# fduino.net
KiCad netlist of a schematic drawn in EAGLE
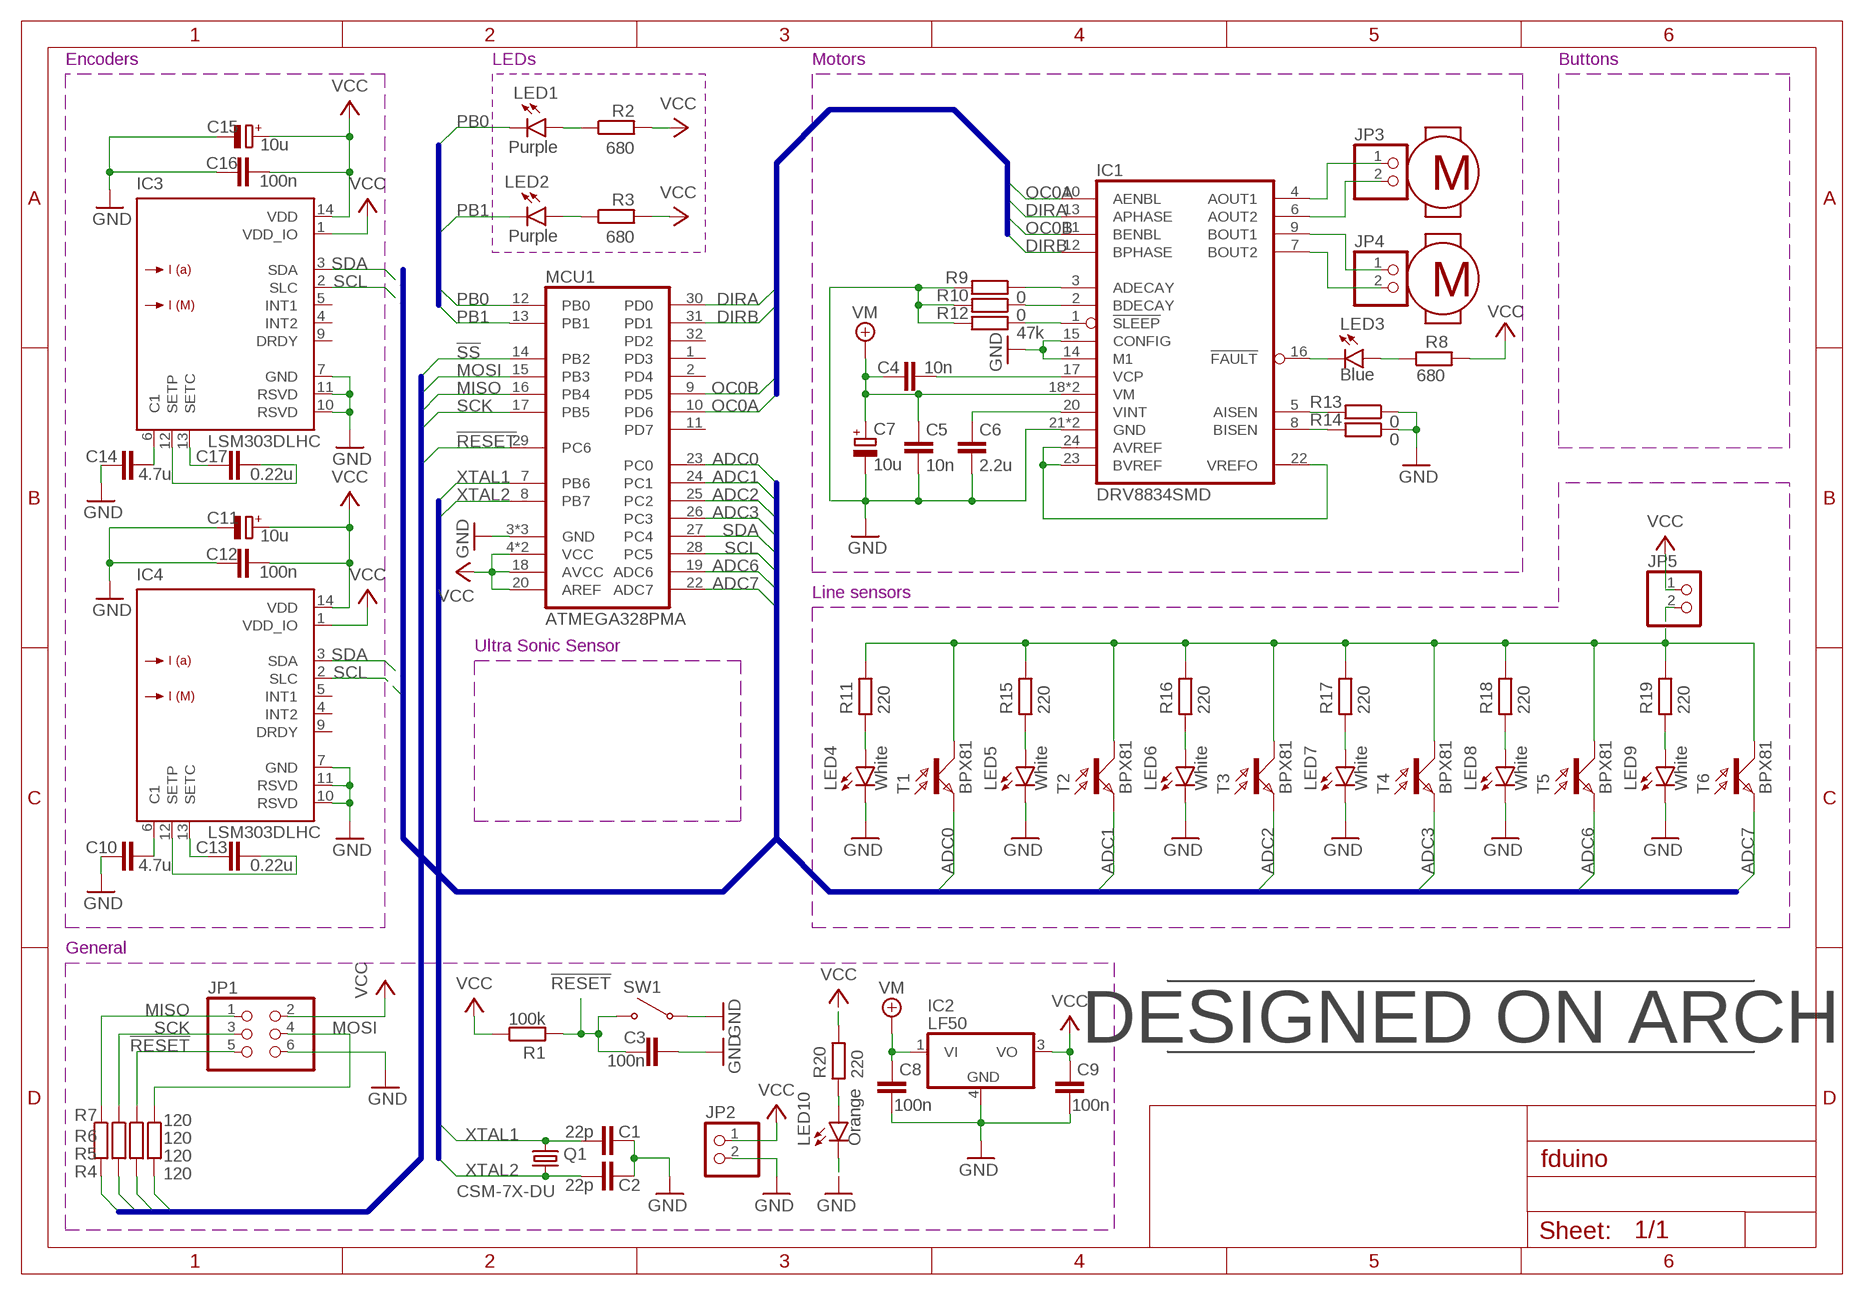
[diagram p0: schematic, sheet 1]

(export (version "E")
  (design (tool "Eeschema 10.0.6"))
  (components
    (comp (ref "C1")
      (value "22p")
      (footprint "eagle-import:C0603")
      (libsource (lib "eagle-import") (part "C-EUC0603"))
    )
    (comp (ref "C2")
      (value "22p")
      (footprint "eagle-import:C0603")
      (libsource (lib "eagle-import") (part "C-EUC0603"))
    )
    (comp (ref "C3")
      (value "100n")
      (footprint "eagle-import:C0603")
      (libsource (lib "eagle-import") (part "C-EUC0603"))
    )
    (comp (ref "C4")
      (value "10n")
      (footprint "eagle-import:C0603")
      (libsource (lib "eagle-import") (part "C-EUC0603"))
    )
    (comp (ref "C5")
      (value "10n")
      (footprint "eagle-import:C0603")
      (libsource (lib "eagle-import") (part "C-EUC0603"))
    )
    (comp (ref "C6")
      (value "2.2u")
      (footprint "eagle-import:C0603")
      (libsource (lib "eagle-import") (part "C-EUC0603"))
    )
    (comp (ref "C7")
      (value "10u")
      (footprint "eagle-import:SMC_Z")
      (libsource (lib "eagle-import") (part "CPOL-EUSMCZ"))
    )
    (comp (ref "C8")
      (value "100n")
      (footprint "eagle-import:C0603")
      (libsource (lib "eagle-import") (part "C-EUC0603"))
    )
    (comp (ref "C9")
      (value "100n")
      (footprint "eagle-import:C0603")
      (libsource (lib "eagle-import") (part "C-EUC0603"))
    )
    (comp (ref "C10")
      (value "4.7u")
      (footprint "eagle-import:C0603")
      (libsource (lib "eagle-import") (part "C-EUC0603"))
    )
    (comp (ref "C11")
      (value "10u")
      (footprint "eagle-import:SMC_Z")
      (libsource (lib "eagle-import") (part "CPOL-EUSMCZ"))
    )
    (comp (ref "C12")
      (value "100n")
      (footprint "eagle-import:C0603")
      (libsource (lib "eagle-import") (part "C-EUC0603"))
    )
    (comp (ref "C13")
      (value "0.22u")
      (footprint "eagle-import:C0603")
      (libsource (lib "eagle-import") (part "C-EUC0603"))
    )
    (comp (ref "C14")
      (value "4.7u")
      (footprint "eagle-import:C0603")
      (libsource (lib "eagle-import") (part "C-EUC0603"))
    )
    (comp (ref "C15")
      (value "10u")
      (footprint "eagle-import:SMC_Z")
      (libsource (lib "eagle-import") (part "CPOL-EUSMCZ"))
    )
    (comp (ref "C16")
      (value "100n")
      (footprint "eagle-import:C0603")
      (libsource (lib "eagle-import") (part "C-EUC0603"))
    )
    (comp (ref "C17")
      (value "0.22u")
      (footprint "eagle-import:C0603")
      (libsource (lib "eagle-import") (part "C-EUC0603"))
    )
    (comp (ref "IC1")
      (value "DRV8834SMD")
      (footprint "eagle-import:HTSSOP")
      (libsource (lib "eagle-import") (part "DRV8834SMD"))
    )
    (comp (ref "IC2")
      (value "LF50")
      (footprint "eagle-import:SOT223")
      (libsource (lib "eagle-import") (part "LM340?-MP05"))
    )
    (comp (ref "IC3")
      (value "LSM303DLHC")
      (footprint "eagle-import:LGA-14")
      (libsource (lib "eagle-import") (part "LSM303DLHC"))
    )
    (comp (ref "IC4")
      (value "LSM303DLHC")
      (footprint "eagle-import:LGA-14")
      (libsource (lib "eagle-import") (part "LSM303DLHC"))
    )
    (comp (ref "JP1")
      (value "PINHD-2X3")
      (footprint "eagle-import:2X03")
      (libsource (lib "eagle-import") (part "PINHD-2X3"))
    )
    (comp (ref "JP2")
      (value "PINHD-1X2")
      (footprint "eagle-import:1X02")
      (libsource (lib "eagle-import") (part "PINHD-1X2"))
    )
    (comp (ref "JP3")
      (value "PINHD-1X2")
      (footprint "eagle-import:1X02")
      (libsource (lib "eagle-import") (part "PINHD-1X2"))
    )
    (comp (ref "JP4")
      (value "PINHD-1X2")
      (footprint "eagle-import:1X02")
      (libsource (lib "eagle-import") (part "PINHD-1X2"))
    )
    (comp (ref "JP5")
      (value "PINHD-1X2")
      (footprint "eagle-import:1X02")
      (libsource (lib "eagle-import") (part "PINHD-1X2"))
    )
    (comp (ref "LED1")
      (value "Purple")
      (footprint "eagle-import:SML0603")
      (libsource (lib "eagle-import") (part "LEDSML0603"))
    )
    (comp (ref "LED2")
      (value "Purple")
      (footprint "eagle-import:SML0603")
      (libsource (lib "eagle-import") (part "LEDSML0603"))
    )
    (comp (ref "LED3")
      (value "Blue")
      (footprint "eagle-import:SML0603")
      (libsource (lib "eagle-import") (part "LEDSML0603"))
    )
    (comp (ref "LED4")
      (value "White")
      (footprint "eagle-import:SML0603")
      (libsource (lib "eagle-import") (part "LEDSML0603"))
    )
    (comp (ref "LED5")
      (value "White")
      (footprint "eagle-import:SML0603")
      (libsource (lib "eagle-import") (part "LEDSML0603"))
    )
    (comp (ref "LED6")
      (value "White")
      (footprint "eagle-import:SML0603")
      (libsource (lib "eagle-import") (part "LEDSML0603"))
    )
    (comp (ref "LED7")
      (value "White")
      (footprint "eagle-import:SML0603")
      (libsource (lib "eagle-import") (part "LEDSML0603"))
    )
    (comp (ref "LED8")
      (value "White")
      (footprint "eagle-import:SML0603")
      (libsource (lib "eagle-import") (part "LEDSML0603"))
    )
    (comp (ref "LED9")
      (value "White")
      (footprint "eagle-import:SML0603")
      (libsource (lib "eagle-import") (part "LEDSML0603"))
    )
    (comp (ref "LED10")
      (value "Orange")
      (footprint "eagle-import:SML0603")
      (libsource (lib "eagle-import") (part "LEDSML0603"))
    )
    (comp (ref "MCU1")
      (value "ATMEGA328PMA")
      (footprint "eagle-import:TQFP32")
      (libsource (lib "eagle-import") (part "ATMEGA328PMA"))
    )
    (comp (ref "Q1")
      (value "CSM-7X-DU")
      (footprint "eagle-import:CSM-7X-DU")
      (libsource (lib "eagle-import") (part "CSM-7X-DU"))
    )
    (comp (ref "R1")
      (value "100k")
      (footprint "eagle-import:R0603")
      (libsource (lib "eagle-import") (part "R-EU_R0603"))
    )
    (comp (ref "R2")
      (value "680")
      (footprint "eagle-import:R0603")
      (libsource (lib "eagle-import") (part "R-EU_R0603"))
    )
    (comp (ref "R3")
      (value "680")
      (footprint "eagle-import:R0603")
      (libsource (lib "eagle-import") (part "R-EU_R0603"))
    )
    (comp (ref "R4")
      (value "120")
      (footprint "eagle-import:R0603")
      (libsource (lib "eagle-import") (part "R-EU_R0603"))
    )
    (comp (ref "R5")
      (value "120")
      (footprint "eagle-import:R0603")
      (libsource (lib "eagle-import") (part "R-EU_R0603"))
    )
    (comp (ref "R6")
      (value "120")
      (footprint "eagle-import:R0603")
      (libsource (lib "eagle-import") (part "R-EU_R0603"))
    )
    (comp (ref "R7")
      (value "120")
      (footprint "eagle-import:R0603")
      (libsource (lib "eagle-import") (part "R-EU_R0603"))
    )
    (comp (ref "R8")
      (value "680")
      (footprint "eagle-import:R0603")
      (libsource (lib "eagle-import") (part "R-EU_R0603"))
    )
    (comp (ref "R9")
      (value "0")
      (footprint "eagle-import:R0603")
      (libsource (lib "eagle-import") (part "R-EU_R0603"))
    )
    (comp (ref "R10")
      (value "0")
      (footprint "eagle-import:R0603")
      (libsource (lib "eagle-import") (part "R-EU_R0603"))
    )
    (comp (ref "R11")
      (value "220")
      (footprint "eagle-import:R0603")
      (libsource (lib "eagle-import") (part "R-EU_R0603"))
    )
    (comp (ref "R12")
      (value "47k")
      (footprint "eagle-import:R0603")
      (libsource (lib "eagle-import") (part "R-EU_R0603"))
    )
    (comp (ref "R13")
      (value "0")
      (footprint "eagle-import:R0603")
      (libsource (lib "eagle-import") (part "R-EU_R0603"))
    )
    (comp (ref "R14")
      (value "0")
      (footprint "eagle-import:R0603")
      (libsource (lib "eagle-import") (part "R-EU_R0603"))
    )
    (comp (ref "R15")
      (value "220")
      (footprint "eagle-import:R0603")
      (libsource (lib "eagle-import") (part "R-EU_R0603"))
    )
    (comp (ref "R16")
      (value "220")
      (footprint "eagle-import:R0603")
      (libsource (lib "eagle-import") (part "R-EU_R0603"))
    )
    (comp (ref "R17")
      (value "220")
      (footprint "eagle-import:R0603")
      (libsource (lib "eagle-import") (part "R-EU_R0603"))
    )
    (comp (ref "R18")
      (value "220")
      (footprint "eagle-import:R0603")
      (libsource (lib "eagle-import") (part "R-EU_R0603"))
    )
    (comp (ref "R19")
      (value "220")
      (footprint "eagle-import:R0603")
      (libsource (lib "eagle-import") (part "R-EU_R0603"))
    )
    (comp (ref "R20")
      (value "220")
      (footprint "eagle-import:R0603")
      (libsource (lib "eagle-import") (part "R-EU_R0603"))
    )
    (comp (ref "SW1")
      (value "SWITCHTHT")
      (footprint "eagle-import:SWITCH")
      (libsource (lib "eagle-import") (part "SWITCHTHT"))
    )
    (comp (ref "T1")
      (value "BPX81")
      (footprint "eagle-import:BPX81")
      (libsource (lib "eagle-import") (part "BPX81"))
    )
    (comp (ref "T2")
      (value "BPX81")
      (footprint "eagle-import:BPX81")
      (libsource (lib "eagle-import") (part "BPX81"))
    )
    (comp (ref "T3")
      (value "BPX81")
      (footprint "eagle-import:BPX81")
      (libsource (lib "eagle-import") (part "BPX81"))
    )
    (comp (ref "T4")
      (value "BPX81")
      (footprint "eagle-import:BPX81")
      (libsource (lib "eagle-import") (part "BPX81"))
    )
    (comp (ref "T5")
      (value "BPX81")
      (footprint "eagle-import:BPX81")
      (libsource (lib "eagle-import") (part "BPX81"))
    )
    (comp (ref "T6")
      (value "BPX81")
      (footprint "eagle-import:BPX81")
      (libsource (lib "eagle-import") (part "BPX81"))
    )
  )
  (nets
    (net (code "1") (name "/ADC0") (class "Default")
      (node (ref "MCU1") (pin "23") (pinfunction "PC0_23") (pintype "bidirectional"))
      (node (ref "T1") (pin "E") (pinfunction "E_E") (pintype "passive"))
    )
    (net (code "2") (name "/ADC1") (class "Default")
      (node (ref "MCU1") (pin "24") (pinfunction "PC1_24") (pintype "bidirectional"))
      (node (ref "T2") (pin "E") (pinfunction "E_E") (pintype "passive"))
    )
    (net (code "3") (name "/ADC2") (class "Default")
      (node (ref "MCU1") (pin "25") (pinfunction "PC2_25") (pintype "bidirectional"))
      (node (ref "T3") (pin "E") (pinfunction "E_E") (pintype "passive"))
    )
    (net (code "4") (name "/ADC3") (class "Default")
      (node (ref "MCU1") (pin "26") (pinfunction "PC3_26") (pintype "bidirectional"))
      (node (ref "T4") (pin "E") (pinfunction "E_E") (pintype "passive"))
    )
    (net (code "5") (name "/ADC6") (class "Default")
      (node (ref "MCU1") (pin "19") (pinfunction "ADC6_19") (pintype "bidirectional"))
      (node (ref "T5") (pin "E") (pinfunction "E_E") (pintype "passive"))
    )
    (net (code "6") (name "/ADC7") (class "Default")
      (node (ref "MCU1") (pin "22") (pinfunction "ADC7_22") (pintype "bidirectional"))
      (node (ref "T6") (pin "E") (pinfunction "E_E") (pintype "passive"))
    )
    (net (code "7") (name "/DIRA") (class "Default")
      (node (ref "IC1") (pin "13") (pinfunction "APHASE_13") (pintype "input"))
      (node (ref "MCU1") (pin "30") (pinfunction "PD0_30") (pintype "bidirectional"))
    )
    (net (code "8") (name "/DIRB") (class "Default")
      (node (ref "IC1") (pin "12") (pinfunction "BPHASE_12") (pintype "input"))
      (node (ref "MCU1") (pin "31") (pinfunction "PD1_31") (pintype "bidirectional"))
    )
    (net (code "9") (name "/MISO") (class "Default")
      (node (ref "JP1") (pin "1") (pinfunction "1_1") (pintype "passive"))
      (node (ref "MCU1") (pin "16") (pinfunction "PB4_16") (pintype "bidirectional"))
      (node (ref "R7") (pin "1") (pinfunction "1_1") (pintype "passive"))
      (node (ref "R7") (pin "2") (pinfunction "2_2") (pintype "passive"))
    )
    (net (code "10") (name "/MOSI") (class "Default")
      (node (ref "JP1") (pin "4") (pinfunction "4_4") (pintype "passive"))
      (node (ref "MCU1") (pin "15") (pinfunction "PB3_15") (pintype "bidirectional"))
      (node (ref "R4") (pin "1") (pinfunction "1_1") (pintype "passive"))
      (node (ref "R4") (pin "2") (pinfunction "2_2") (pintype "passive"))
    )
    (net (code "11") (name "/OC0A") (class "Default")
      (node (ref "IC1") (pin "10") (pinfunction "AENBL_10") (pintype "input"))
      (node (ref "MCU1") (pin "10") (pinfunction "PD6_10") (pintype "bidirectional"))
    )
    (net (code "12") (name "/OC0B") (class "Default")
      (node (ref "IC1") (pin "11") (pinfunction "BENBL_11") (pintype "input"))
      (node (ref "MCU1") (pin "9") (pinfunction "PD5_9") (pintype "bidirectional"))
    )
    (net (code "13") (name "/PB0") (class "Default")
      (node (ref "LED1") (pin "C") (pinfunction "C_C") (pintype "passive"))
      (node (ref "MCU1") (pin "12") (pinfunction "PB0_12") (pintype "bidirectional"))
    )
    (net (code "14") (name "/PB1") (class "Default")
      (node (ref "LED2") (pin "C") (pinfunction "C_C") (pintype "passive"))
      (node (ref "MCU1") (pin "13") (pinfunction "PB1_13") (pintype "bidirectional"))
    )
    (net (code "15") (name "/SCK") (class "Default")
      (node (ref "JP1") (pin "3") (pinfunction "3_3") (pintype "passive"))
      (node (ref "MCU1") (pin "17") (pinfunction "PB5_17") (pintype "output"))
      (node (ref "R6") (pin "1") (pinfunction "1_1") (pintype "passive"))
      (node (ref "R6") (pin "2") (pinfunction "2_2") (pintype "passive"))
    )
    (net (code "16") (name "/SCL") (class "Default")
      (node (ref "IC3") (pin "2") (pinfunction "SLC_2") (pintype "bidirectional"))
      (node (ref "IC4") (pin "2") (pinfunction "SLC_2") (pintype "bidirectional"))
      (node (ref "MCU1") (pin "28") (pinfunction "PC5_28") (pintype "bidirectional"))
    )
    (net (code "17") (name "/SDA") (class "Default")
      (node (ref "IC3") (pin "3") (pinfunction "SDA_3") (pintype "bidirectional"))
      (node (ref "IC4") (pin "3") (pinfunction "SDA_3") (pintype "bidirectional"))
      (node (ref "MCU1") (pin "27") (pinfunction "PC4_27") (pintype "bidirectional"))
    )
    (net (code "18") (name "/XTAL1") (class "Default")
      (node (ref "C1") (pin "2") (pinfunction "2_2") (pintype "passive"))
      (node (ref "MCU1") (pin "7") (pinfunction "PB6_7") (pintype "power_in"))
      (node (ref "Q1") (pin "2") (pinfunction "2_2") (pintype "passive"))
    )
    (net (code "19") (name "/XTAL2") (class "Default")
      (node (ref "C2") (pin "2") (pinfunction "2_2") (pintype "passive"))
      (node (ref "MCU1") (pin "8") (pinfunction "PB7_8") (pintype "input"))
      (node (ref "Q1") (pin "1") (pinfunction "1_1") (pintype "passive"))
    )
    (net (code "20") (name "/~{RESET}") (class "Default")
      (node (ref "C3") (pin "1") (pinfunction "1_1") (pintype "passive"))
      (node (ref "JP1") (pin "5") (pinfunction "5_5") (pintype "passive"))
      (node (ref "MCU1") (pin "29") (pinfunction "PC6_29") (pintype "input"))
      (node (ref "R1") (pin "2") (pinfunction "2_2") (pintype "passive"))
      (node (ref "R5") (pin "1") (pinfunction "1_1") (pintype "passive"))
      (node (ref "R5") (pin "2") (pinfunction "2_2") (pintype "passive"))
      (node (ref "SW1") (pin "P$2") (pinfunction "2_P$2") (pintype "passive"))
    )
    (net (code "21") (name "/~{SS}") (class "Default")
      (node (ref "MCU1") (pin "14") (pinfunction "PB2_14") (pintype "bidirectional"))
    )
    (net (code "22") (name "GND") (class "Default")
      (node (ref "C1") (pin "1") (pinfunction "1_1") (pintype "passive"))
      (node (ref "C10") (pin "2") (pinfunction "2_2") (pintype "passive"))
      (node (ref "C11") (pin "-") (pinfunction "-_-") (pintype "passive"))
      (node (ref "C12") (pin "1") (pinfunction "1_1") (pintype "passive"))
      (node (ref "C14") (pin "2") (pinfunction "2_2") (pintype "passive"))
      (node (ref "C15") (pin "-") (pinfunction "-_-") (pintype "passive"))
      (node (ref "C16") (pin "1") (pinfunction "1_1") (pintype "passive"))
      (node (ref "C2") (pin "1") (pinfunction "1_1") (pintype "passive"))
      (node (ref "C3") (pin "2") (pinfunction "2_2") (pintype "passive"))
      (node (ref "C5") (pin "2") (pinfunction "2_2") (pintype "passive"))
      (node (ref "C6") (pin "2") (pinfunction "2_2") (pintype "passive"))
      (node (ref "C7") (pin "-") (pinfunction "-_-") (pintype "passive"))
      (node (ref "C8") (pin "2") (pinfunction "2_2") (pintype "passive"))
      (node (ref "C9") (pin "2") (pinfunction "2_2") (pintype "passive"))
      (node (ref "IC1") (pin "14") (pinfunction "M1_14") (pintype "input"))
      (node (ref "IC1") (pin "15") (pinfunction "CONFIG_15") (pintype "input"))
      (node (ref "IC1") (pin "21") (pinfunction "GND_21") (pintype "input"))
      (node (ref "IC1") (pin "PPAD") (pinfunction "GND_PPAD") (pintype "input"))
      (node (ref "IC2") (pin "4") (pinfunction "GND_4") (pintype "passive"))
      (node (ref "IC3") (pin "10") (pinfunction "RSVD_10") (pintype "passive"))
      (node (ref "IC3") (pin "11") (pinfunction "RSVD_11") (pintype "passive"))
      (node (ref "IC3") (pin "7") (pinfunction "GND_7") (pintype "power_in"))
      (node (ref "IC4") (pin "10") (pinfunction "RSVD_10") (pintype "passive"))
      (node (ref "IC4") (pin "11") (pinfunction "RSVD_11") (pintype "passive"))
      (node (ref "IC4") (pin "7") (pinfunction "GND_7") (pintype "power_in"))
      (node (ref "JP1") (pin "6") (pinfunction "6_6") (pintype "passive"))
      (node (ref "JP2") (pin "2") (pinfunction "2_2") (pintype "passive"))
      (node (ref "LED10") (pin "C") (pinfunction "C_C") (pintype "passive"))
      (node (ref "LED4") (pin "C") (pinfunction "C_C") (pintype "passive"))
      (node (ref "LED5") (pin "C") (pinfunction "C_C") (pintype "passive"))
      (node (ref "LED6") (pin "C") (pinfunction "C_C") (pintype "passive"))
      (node (ref "LED7") (pin "C") (pinfunction "C_C") (pintype "passive"))
      (node (ref "LED8") (pin "C") (pinfunction "C_C") (pintype "passive"))
      (node (ref "LED9") (pin "C") (pinfunction "C_C") (pintype "passive"))
      (node (ref "MCU1") (pin "21") (pinfunction "GND_21") (pintype "bidirectional"))
      (node (ref "MCU1") (pin "3") (pinfunction "GND_3") (pintype "bidirectional"))
      (node (ref "MCU1") (pin "5") (pinfunction "GND_5") (pintype "bidirectional"))
      (node (ref "R13") (pin "1") (pinfunction "1_1") (pintype "passive"))
      (node (ref "R14") (pin "1") (pinfunction "1_1") (pintype "passive"))
      (node (ref "SW1") (pin "P$1") (pinfunction "1_P$1") (pintype "passive"))
    )
    (net (code "23") (name "Net-(IC1-ADECAY)") (class "Default")
      (node (ref "IC1") (pin "3") (pinfunction "ADECAY_3") (pintype "input"))
      (node (ref "R9") (pin "1") (pinfunction "1_1") (pintype "passive"))
    )
    (net (code "24") (name "Net-(IC1-AISEN)") (class "Default")
      (node (ref "IC1") (pin "5") (pinfunction "AISEN_5") (pintype "output"))
      (node (ref "R13") (pin "2") (pinfunction "2_2") (pintype "passive"))
    )
    (net (code "25") (name "Net-(IC1-AOUT1)") (class "Default")
      (node (ref "IC1") (pin "4") (pinfunction "AOUT1_4") (pintype "output"))
      (node (ref "JP3") (pin "1") (pinfunction "1_1") (pintype "passive"))
    )
    (net (code "26") (name "Net-(IC1-AOUT2)") (class "Default")
      (node (ref "IC1") (pin "6") (pinfunction "AOUT2_6") (pintype "output"))
      (node (ref "JP3") (pin "2") (pinfunction "2_2") (pintype "passive"))
    )
    (net (code "27") (name "Net-(IC1-AVREF)") (class "Default")
      (node (ref "IC1") (pin "22") (pinfunction "VREFO_22") (pintype "output"))
      (node (ref "IC1") (pin "23") (pinfunction "BVREF_23") (pintype "input"))
      (node (ref "IC1") (pin "24") (pinfunction "AVREF_24") (pintype "input"))
    )
    (net (code "28") (name "Net-(IC1-BDECAY)") (class "Default")
      (node (ref "IC1") (pin "2") (pinfunction "BDECAY_2") (pintype "input"))
      (node (ref "R10") (pin "1") (pinfunction "1_1") (pintype "passive"))
    )
    (net (code "29") (name "Net-(IC1-BISEN)") (class "Default")
      (node (ref "IC1") (pin "8") (pinfunction "BISEN_8") (pintype "output"))
      (node (ref "R14") (pin "2") (pinfunction "2_2") (pintype "passive"))
    )
    (net (code "30") (name "Net-(IC1-BOUT1)") (class "Default")
      (node (ref "IC1") (pin "9") (pinfunction "BOUT1_9") (pintype "output"))
      (node (ref "JP4") (pin "1") (pinfunction "1_1") (pintype "passive"))
    )
    (net (code "31") (name "Net-(IC1-BOUT2)") (class "Default")
      (node (ref "IC1") (pin "7") (pinfunction "BOUT2_7") (pintype "output"))
      (node (ref "JP4") (pin "2") (pinfunction "2_2") (pintype "passive"))
    )
    (net (code "32") (name "Net-(IC1-VCP)") (class "Default")
      (node (ref "C4") (pin "2") (pinfunction "2_2") (pintype "passive"))
      (node (ref "IC1") (pin "17") (pinfunction "VCP_17") (pintype "input"))
    )
    (net (code "33") (name "Net-(IC1-VINT)") (class "Default")
      (node (ref "C6") (pin "1") (pinfunction "1_1") (pintype "passive"))
      (node (ref "IC1") (pin "20") (pinfunction "VINT_20") (pintype "input"))
    )
    (net (code "34") (name "Net-(IC1-~{FAULT})") (class "Default")
      (node (ref "IC1") (pin "16") (pinfunction "~{FAULT}_16") (pintype "output"))
      (node (ref "LED3") (pin "C") (pinfunction "C_C") (pintype "passive"))
    )
    (net (code "35") (name "Net-(IC1-~{SLEEP})") (class "Default")
      (node (ref "IC1") (pin "1") (pinfunction "~{SLEEP}_1") (pintype "input"))
      (node (ref "R12") (pin "1") (pinfunction "1_1") (pintype "passive"))
    )
    (net (code "36") (name "Net-(IC3-C1)") (class "Default")
      (node (ref "C14") (pin "1") (pinfunction "1_1") (pintype "passive"))
      (node (ref "IC3") (pin "6") (pinfunction "C1_6") (pintype "passive"))
    )
    (net (code "37") (name "Net-(IC3-SETC)") (class "Default")
      (node (ref "C17") (pin "1") (pinfunction "1_1") (pintype "passive"))
      (node (ref "IC3") (pin "13") (pinfunction "SETC_13") (pintype "passive"))
    )
    (net (code "38") (name "Net-(IC3-SETP)") (class "Default")
      (node (ref "C17") (pin "2") (pinfunction "2_2") (pintype "passive"))
      (node (ref "IC3") (pin "12") (pinfunction "SETP_12") (pintype "passive"))
    )
    (net (code "39") (name "Net-(IC4-C1)") (class "Default")
      (node (ref "C10") (pin "1") (pinfunction "1_1") (pintype "passive"))
      (node (ref "IC4") (pin "6") (pinfunction "C1_6") (pintype "passive"))
    )
    (net (code "40") (name "Net-(IC4-SETC)") (class "Default")
      (node (ref "C13") (pin "1") (pinfunction "1_1") (pintype "passive"))
      (node (ref "IC4") (pin "13") (pinfunction "SETC_13") (pintype "passive"))
    )
    (net (code "41") (name "Net-(IC4-SETP)") (class "Default")
      (node (ref "C13") (pin "2") (pinfunction "2_2") (pintype "passive"))
      (node (ref "IC4") (pin "12") (pinfunction "SETP_12") (pintype "passive"))
    )
    (net (code "42") (name "Net-(JP5-Pad2)") (class "Default")
      (node (ref "JP5") (pin "2") (pinfunction "2_2") (pintype "passive"))
      (node (ref "T1") (pin "C") (pinfunction "C_C") (pintype "passive"))
      (node (ref "T2") (pin "C") (pinfunction "C_C") (pintype "passive"))
      (node (ref "T3") (pin "C") (pinfunction "C_C") (pintype "passive"))
      (node (ref "T4") (pin "C") (pinfunction "C_C") (pintype "passive"))
      (node (ref "T5") (pin "C") (pinfunction "C_C") (pintype "passive"))
      (node (ref "T6") (pin "C") (pinfunction "C_C") (pintype "passive"))
    )
    (net (code "43") (name "Net-(LED1-PadA)") (class "Default")
      (node (ref "LED1") (pin "A") (pinfunction "A_A") (pintype "passive"))
      (node (ref "R2") (pin "1") (pinfunction "1_1") (pintype "passive"))
    )
    (net (code "44") (name "Net-(LED2-PadA)") (class "Default")
      (node (ref "LED2") (pin "A") (pinfunction "A_A") (pintype "passive"))
      (node (ref "R3") (pin "1") (pinfunction "1_1") (pintype "passive"))
    )
    (net (code "45") (name "Net-(LED3-PadA)") (class "Default")
      (node (ref "LED3") (pin "A") (pinfunction "A_A") (pintype "passive"))
      (node (ref "R8") (pin "1") (pinfunction "1_1") (pintype "passive"))
    )
    (net (code "46") (name "Net-(LED4-PadA)") (class "Default")
      (node (ref "LED4") (pin "A") (pinfunction "A_A") (pintype "passive"))
      (node (ref "R11") (pin "2") (pinfunction "2_2") (pintype "passive"))
    )
    (net (code "47") (name "Net-(LED5-PadA)") (class "Default")
      (node (ref "LED5") (pin "A") (pinfunction "A_A") (pintype "passive"))
      (node (ref "R15") (pin "2") (pinfunction "2_2") (pintype "passive"))
    )
    (net (code "48") (name "Net-(LED6-PadA)") (class "Default")
      (node (ref "LED6") (pin "A") (pinfunction "A_A") (pintype "passive"))
      (node (ref "R16") (pin "2") (pinfunction "2_2") (pintype "passive"))
    )
    (net (code "49") (name "Net-(LED7-PadA)") (class "Default")
      (node (ref "LED7") (pin "A") (pinfunction "A_A") (pintype "passive"))
      (node (ref "R17") (pin "2") (pinfunction "2_2") (pintype "passive"))
    )
    (net (code "50") (name "Net-(LED8-PadA)") (class "Default")
      (node (ref "LED8") (pin "A") (pinfunction "A_A") (pintype "passive"))
      (node (ref "R18") (pin "2") (pinfunction "2_2") (pintype "passive"))
    )
    (net (code "51") (name "Net-(LED9-PadA)") (class "Default")
      (node (ref "LED9") (pin "A") (pinfunction "A_A") (pintype "passive"))
      (node (ref "R19") (pin "2") (pinfunction "2_2") (pintype "passive"))
    )
    (net (code "52") (name "Net-(LED10-PadA)") (class "Default")
      (node (ref "LED10") (pin "A") (pinfunction "A_A") (pintype "passive"))
      (node (ref "R20") (pin "2") (pinfunction "2_2") (pintype "passive"))
    )
    (net (code "53") (name "Net-(R10-Pad2)") (class "Default")
      (node (ref "R10") (pin "2") (pinfunction "2_2") (pintype "passive"))
      (node (ref "R12") (pin "2") (pinfunction "2_2") (pintype "passive"))
      (node (ref "R9") (pin "2") (pinfunction "2_2") (pintype "passive"))
    )
    (net (code "54") (name "VCC") (class "Default")
      (node (ref "C11") (pin "+") (pinfunction "+_+") (pintype "passive"))
      (node (ref "C12") (pin "2") (pinfunction "2_2") (pintype "passive"))
      (node (ref "C15") (pin "+") (pinfunction "+_+") (pintype "passive"))
      (node (ref "C16") (pin "2") (pinfunction "2_2") (pintype "passive"))
      (node (ref "C9") (pin "1") (pinfunction "1_1") (pintype "passive"))
      (node (ref "IC2") (pin "3") (pinfunction "VO_3") (pintype "passive"))
      (node (ref "IC3") (pin "1") (pinfunction "VDD_IO_1") (pintype "power_in"))
      (node (ref "IC3") (pin "14") (pinfunction "VDD_14") (pintype "power_in"))
      (node (ref "IC4") (pin "1") (pinfunction "VDD_IO_1") (pintype "power_in"))
      (node (ref "IC4") (pin "14") (pinfunction "VDD_14") (pintype "power_in"))
      (node (ref "JP1") (pin "2") (pinfunction "2_2") (pintype "passive"))
      (node (ref "JP2") (pin "1") (pinfunction "1_1") (pintype "passive"))
      (node (ref "MCU1") (pin "18") (pinfunction "AVCC_18") (pintype "bidirectional"))
      (node (ref "MCU1") (pin "20") (pinfunction "AREF_20") (pintype "bidirectional"))
      (node (ref "MCU1") (pin "4") (pinfunction "VCC_4") (pintype "bidirectional"))
      (node (ref "MCU1") (pin "6") (pinfunction "VCC_6") (pintype "bidirectional"))
      (node (ref "R1") (pin "1") (pinfunction "1_1") (pintype "passive"))
      (node (ref "R2") (pin "2") (pinfunction "2_2") (pintype "passive"))
      (node (ref "R20") (pin "1") (pinfunction "1_1") (pintype "passive"))
      (node (ref "R3") (pin "2") (pinfunction "2_2") (pintype "passive"))
      (node (ref "R8") (pin "2") (pinfunction "2_2") (pintype "passive"))
    )
    (net (code "55") (name "VM") (class "Default")
      (node (ref "C4") (pin "1") (pinfunction "1_1") (pintype "passive"))
      (node (ref "C5") (pin "1") (pinfunction "1_1") (pintype "passive"))
      (node (ref "C7") (pin "+") (pinfunction "+_+") (pintype "passive"))
      (node (ref "C8") (pin "1") (pinfunction "1_1") (pintype "passive"))
      (node (ref "IC1") (pin "18") (pinfunction "VM_18") (pintype "input"))
      (node (ref "IC1") (pin "19") (pinfunction "VM_19") (pintype "input"))
      (node (ref "IC2") (pin "1") (pinfunction "VI_1") (pintype "input"))
    )
    (net (code "56") (name "unconnected-(IC3-DRDY-Pad9)") (class "Default")
      (node (ref "IC3") (pin "9") (pinfunction "DRDY_9") (pintype "bidirectional"))
    )
    (net (code "57") (name "unconnected-(IC3-INT1-Pad5)") (class "Default")
      (node (ref "IC3") (pin "5") (pinfunction "INT1_5") (pintype "bidirectional"))
    )
    (net (code "58") (name "unconnected-(IC3-INT2-Pad4)") (class "Default")
      (node (ref "IC3") (pin "4") (pinfunction "INT2_4") (pintype "bidirectional"))
    )
    (net (code "59") (name "unconnected-(IC4-DRDY-Pad9)") (class "Default")
      (node (ref "IC4") (pin "9") (pinfunction "DRDY_9") (pintype "bidirectional"))
    )
    (net (code "60") (name "unconnected-(IC4-INT1-Pad5)") (class "Default")
      (node (ref "IC4") (pin "5") (pinfunction "INT1_5") (pintype "bidirectional"))
    )
    (net (code "61") (name "unconnected-(IC4-INT2-Pad4)") (class "Default")
      (node (ref "IC4") (pin "4") (pinfunction "INT2_4") (pintype "bidirectional"))
    )
    (net (code "62") (name "unconnected-(JP5-Pad1)") (class "Default")
      (node (ref "JP5") (pin "1") (pinfunction "1_1") (pintype "passive"))
    )
    (net (code "63") (name "unconnected-(MCU1-PD2-Pad32)") (class "Default")
      (node (ref "MCU1") (pin "32") (pinfunction "PD2_32") (pintype "bidirectional"))
    )
    (net (code "64") (name "unconnected-(MCU1-PD3-Pad1)") (class "Default")
      (node (ref "MCU1") (pin "1") (pinfunction "PD3_1") (pintype "bidirectional"))
    )
    (net (code "65") (name "unconnected-(MCU1-PD4-Pad2)") (class "Default")
      (node (ref "MCU1") (pin "2") (pinfunction "PD4_2") (pintype "bidirectional"))
    )
    (net (code "66") (name "unconnected-(MCU1-PD7-Pad11)") (class "Default")
      (node (ref "MCU1") (pin "11") (pinfunction "PD7_11") (pintype "bidirectional"))
    )
    (net (code "67") (name "unconnected-(R11-Pad1)") (class "Default")
      (node (ref "R11") (pin "1") (pinfunction "1_1") (pintype "passive"))
    )
    (net (code "68") (name "unconnected-(R15-Pad1)") (class "Default")
      (node (ref "R15") (pin "1") (pinfunction "1_1") (pintype "passive"))
    )
    (net (code "69") (name "unconnected-(R16-Pad1)") (class "Default")
      (node (ref "R16") (pin "1") (pinfunction "1_1") (pintype "passive"))
    )
    (net (code "70") (name "unconnected-(R17-Pad1)") (class "Default")
      (node (ref "R17") (pin "1") (pinfunction "1_1") (pintype "passive"))
    )
    (net (code "71") (name "unconnected-(R18-Pad1)") (class "Default")
      (node (ref "R18") (pin "1") (pinfunction "1_1") (pintype "passive"))
    )
    (net (code "72") (name "unconnected-(R19-Pad1)") (class "Default")
      (node (ref "R19") (pin "1") (pinfunction "1_1") (pintype "passive"))
    )
  )
)
